# Device-TesterHat.net
KiCad netlist of a schematic drawn in Altium Designer
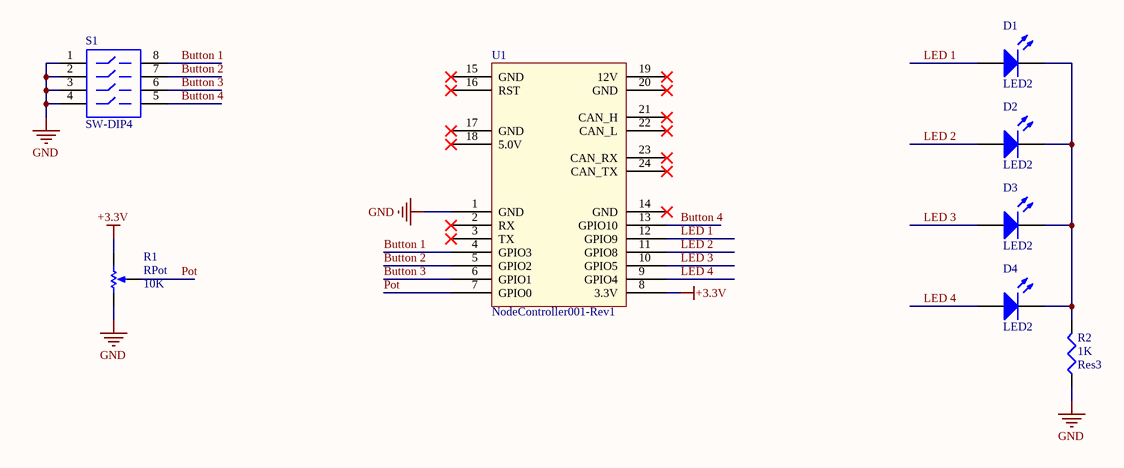
[diagram p0: Device-TesterHat.SchDoc]

(export (version "E")
  (design (tool "Eeschema 10.0.6"))
  (components
    (comp (ref "D1")
      (value "LED2")
      (footprint "3.2X1.6X1.1")
      (description "Typical RED, GREEN, YELLOW, AMBER GaAs LED")
      (fields (field (name "PUBLISHER") "Altium Limited"))
      (libsource (lib "ProjectFishWorks-Schematic") (part "LED2"))
    )
    (comp (ref "D2")
      (value "LED2")
      (footprint "3.2X1.6X1.1")
      (description "Typical RED, GREEN, YELLOW, AMBER GaAs LED")
      (fields (field (name "PUBLISHER") "Altium Limited"))
      (libsource (lib "ProjectFishWorks-Schematic") (part "LED2"))
    )
    (comp (ref "D3")
      (value "LED2")
      (footprint "3.2X1.6X1.1")
      (description "Typical RED, GREEN, YELLOW, AMBER GaAs LED")
      (fields (field (name "PUBLISHER") "Altium Limited"))
      (libsource (lib "ProjectFishWorks-Schematic") (part "LED2"))
    )
    (comp (ref "D4")
      (value "LED2")
      (footprint "3.2X1.6X1.1")
      (description "Typical RED, GREEN, YELLOW, AMBER GaAs LED")
      (fields (field (name "PUBLISHER") "Altium Limited"))
      (libsource (lib "ProjectFishWorks-Schematic") (part "LED2"))
    )
    (comp (ref "R1")
      (value "RPot")
      (footprint "VR5")
      (description "Potentiometer")
      (fields (field (name "ALTIUM_VALUE") "10K") (field (name "PUBLISHER") "Altium Limited"))
      (libsource (lib "ProjectFishWorks-Schematic") (part "RPot"))
    )
    (comp (ref "R2")
      (value "Res3")
      (footprint "J1-0603")
      (description "Resistor")
      (fields (field (name "ALTIUM_VALUE") "1K") (field (name "PUBLISHER") "Altium Limited"))
      (libsource (lib "ProjectFishWorks-Schematic") (part "Res3"))
    )
    (comp (ref "S1")
      (value "SW-DIP4")
      (footprint "DIP-8")
      (description "DIP Switch")
      (fields (field (name "PUBLISHER") "Altium Limited"))
      (libsource (lib "ProjectFishWorks-Schematic") (part "SW-DIP4"))
    )
    (comp (ref "U1")
      (value "NodeController001-Rev1")
      (libsource (lib "ProjectFishWorks-Schematic") (part "NodeController001-Rev1"))
    )
  )
  (nets
    (net (code "1") (name "+3.3V") (class "Default")
      (node (ref "R1") (pin "2") (pinfunction "BOT_2") (pintype "passive"))
      (node (ref "U1") (pin "8") (pinfunction "3.3V_8") (pintype "passive"))
    )
    (net (code "2") (name "/Button 1") (class "Default")
      (node (ref "S1") (pin "8") (pinfunction "8_8") (pintype "passive"))
      (node (ref "U1") (pin "4") (pinfunction "GPIO3_4") (pintype "passive"))
    )
    (net (code "3") (name "/Button 2") (class "Default")
      (node (ref "S1") (pin "7") (pinfunction "7_7") (pintype "passive"))
      (node (ref "U1") (pin "5") (pinfunction "GPIO2_5") (pintype "passive"))
    )
    (net (code "4") (name "/Button 3") (class "Default")
      (node (ref "S1") (pin "6") (pinfunction "6_6") (pintype "passive"))
      (node (ref "U1") (pin "6") (pinfunction "GPIO1_6") (pintype "passive"))
    )
    (net (code "5") (name "/Button 4") (class "Default")
      (node (ref "S1") (pin "5") (pinfunction "5_5") (pintype "passive"))
      (node (ref "U1") (pin "13") (pinfunction "GPIO10_13") (pintype "passive"))
    )
    (net (code "6") (name "/LED 1") (class "Default")
      (node (ref "D1") (pin "1") (pinfunction "A_1") (pintype "passive"))
      (node (ref "U1") (pin "12") (pinfunction "GPIO9_12") (pintype "passive"))
    )
    (net (code "7") (name "/LED 2") (class "Default")
      (node (ref "D2") (pin "1") (pinfunction "A_1") (pintype "passive"))
      (node (ref "U1") (pin "11") (pinfunction "GPIO8_11") (pintype "passive"))
    )
    (net (code "8") (name "/LED 3") (class "Default")
      (node (ref "D3") (pin "1") (pinfunction "A_1") (pintype "passive"))
      (node (ref "U1") (pin "10") (pinfunction "GPIO5_10") (pintype "passive"))
    )
    (net (code "9") (name "/LED 4") (class "Default")
      (node (ref "D4") (pin "1") (pinfunction "A_1") (pintype "passive"))
      (node (ref "U1") (pin "9") (pinfunction "GPIO4_9") (pintype "passive"))
    )
    (net (code "10") (name "/Pot") (class "Default")
      (node (ref "R1") (pin "3") (pinfunction "TAP_3") (pintype "passive"))
      (node (ref "U1") (pin "7") (pinfunction "GPIO0_7") (pintype "passive"))
    )
    (net (code "11") (name "GND") (class "Default")
      (node (ref "R1") (pin "1") (pinfunction "TOP_1") (pintype "passive"))
      (node (ref "R2") (pin "1") (pinfunction "1_1") (pintype "passive"))
      (node (ref "S1") (pin "1") (pinfunction "1_1") (pintype "passive"))
      (node (ref "S1") (pin "2") (pinfunction "2_2") (pintype "passive"))
      (node (ref "S1") (pin "3") (pinfunction "3_3") (pintype "passive"))
      (node (ref "S1") (pin "4") (pinfunction "4_4") (pintype "passive"))
      (node (ref "U1") (pin "1") (pinfunction "GND_1") (pintype "passive"))
    )
    (net (code "12") (name "Net-(D1-K)") (class "Default")
      (node (ref "D1") (pin "2") (pinfunction "K_2") (pintype "passive"))
      (node (ref "D2") (pin "2") (pinfunction "K_2") (pintype "passive"))
      (node (ref "D3") (pin "2") (pinfunction "K_2") (pintype "passive"))
      (node (ref "D4") (pin "2") (pinfunction "K_2") (pintype "passive"))
      (node (ref "R2") (pin "2") (pinfunction "2_2") (pintype "passive"))
    )
    (net (code "13") (name "unconnected-(U1-5.0V-Pad18)") (class "Default")
      (node (ref "U1") (pin "18") (pinfunction "5.0V_18") (pintype "passive+no_connect"))
    )
    (net (code "14") (name "unconnected-(U1-12V-Pad19)") (class "Default")
      (node (ref "U1") (pin "19") (pinfunction "12V_19") (pintype "passive+no_connect"))
    )
    (net (code "15") (name "unconnected-(U1-CAN_H-Pad21)") (class "Default")
      (node (ref "U1") (pin "21") (pinfunction "CAN_H_21") (pintype "passive+no_connect"))
    )
    (net (code "16") (name "unconnected-(U1-CAN_L-Pad22)") (class "Default")
      (node (ref "U1") (pin "22") (pinfunction "CAN_L_22") (pintype "passive+no_connect"))
    )
    (net (code "17") (name "unconnected-(U1-CAN_RX-Pad23)") (class "Default")
      (node (ref "U1") (pin "23") (pinfunction "CAN_RX_23") (pintype "passive+no_connect"))
    )
    (net (code "18") (name "unconnected-(U1-CAN_TX-Pad24)") (class "Default")
      (node (ref "U1") (pin "24") (pinfunction "CAN_TX_24") (pintype "passive+no_connect"))
    )
    (net (code "19") (name "unconnected-(U1-GND-Pad14)") (class "Default")
      (node (ref "U1") (pin "14") (pinfunction "GND_14") (pintype "passive+no_connect"))
    )
    (net (code "20") (name "unconnected-(U1-GND-Pad15)") (class "Default")
      (node (ref "U1") (pin "15") (pinfunction "GND_15") (pintype "passive+no_connect"))
    )
    (net (code "21") (name "unconnected-(U1-GND-Pad17)") (class "Default")
      (node (ref "U1") (pin "17") (pinfunction "GND_17") (pintype "passive+no_connect"))
    )
    (net (code "22") (name "unconnected-(U1-GND-Pad20)") (class "Default")
      (node (ref "U1") (pin "20") (pinfunction "GND_20") (pintype "passive+no_connect"))
    )
    (net (code "23") (name "unconnected-(U1-RST-Pad16)") (class "Default")
      (node (ref "U1") (pin "16") (pinfunction "RST_16") (pintype "passive+no_connect"))
    )
    (net (code "24") (name "unconnected-(U1-RX-Pad2)") (class "Default")
      (node (ref "U1") (pin "2") (pinfunction "RX_2") (pintype "passive+no_connect"))
    )
    (net (code "25") (name "unconnected-(U1-TX-Pad3)") (class "Default")
      (node (ref "U1") (pin "3") (pinfunction "TX_3") (pintype "passive+no_connect"))
    )
  )
)
